# Drone.net
KiCad netlist of a schematic drawn in EAGLE
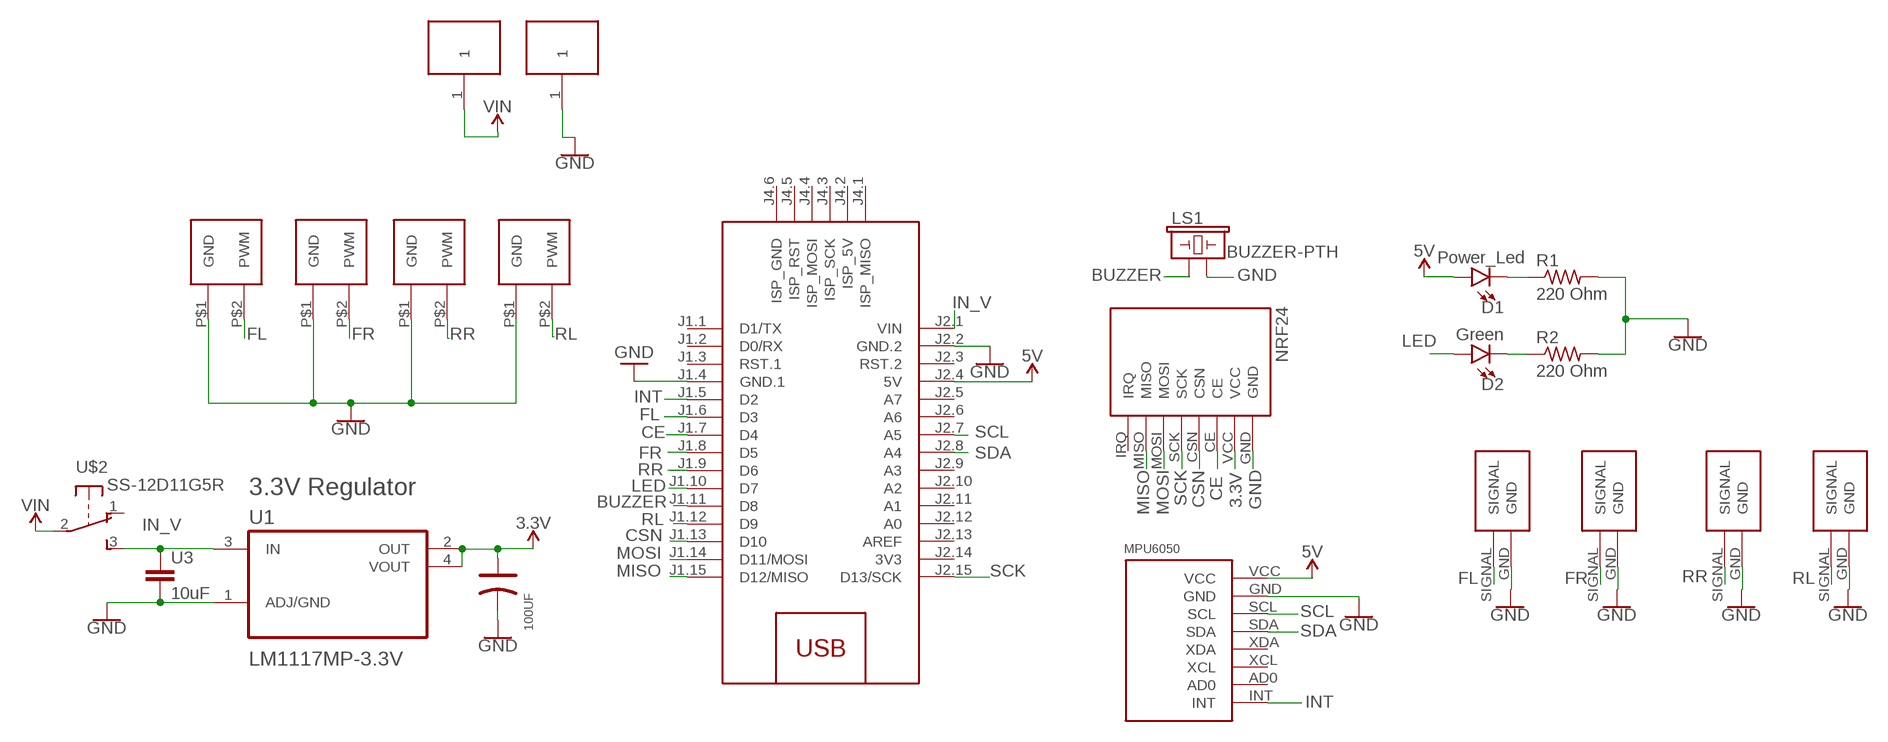
[diagram p0: schematic, sheet 1]

(export (version "E")
  (design (tool "Eeschema 10.0.6"))
  (components
    (comp (ref "D1")
      (value "Power_Led")
      (footprint "eagle-import:LED_5MM")
      (libsource (lib "eagle-import") (part "LED5MM"))
    )
    (comp (ref "D2")
      (value "Green")
      (footprint "eagle-import:LED_5MM")
      (libsource (lib "eagle-import") (part "LED5MM"))
    )
    (comp (ref "LS1")
      (value "BUZZER-PTH")
      (footprint "eagle-import:BUZZER-12MM")
      (libsource (lib "eagle-import") (part "BUZZER-PTH"))
    )
    (comp (ref "M1")
      (value "ARDUINO-NANO-3.0#ISP")
      (footprint "eagle-import:ARDUINO-NANO-3.0#ISP")
      (libsource (lib "eagle-import") (part "ARDUINO-NANO-3.0#ISP"))
    )
    (comp (ref "R1")
      (value "220 Ohm")
      (footprint "eagle-import:RES_1206")
      (fields
        (field (name "DIGIKEY_PART_NUMBER") "P0.0ETR-ND")
        (field (name "MANUFACTURER") "Panasonic Electronic Components")
        (field (name "MPN") "ERJ-8GEY0R00V")
        (field (name "CREATED_BY") "PCBLayout.com")
      )
      (libsource (lib "eagle-import") (part "ERJ-8GEY0R00V"))
    )
    (comp (ref "R2")
      (value "220 Ohm")
      (footprint "eagle-import:RES_1206")
      (fields
        (field (name "DIGIKEY_PART_NUMBER") "P0.0ETR-ND")
        (field (name "MANUFACTURER") "Panasonic Electronic Components")
        (field (name "MPN") "ERJ-8GEY0R00V")
        (field (name "CREATED_BY") "PCBLayout.com")
      )
      (libsource (lib "eagle-import") (part "ERJ-8GEY0R00V"))
    )
    (comp (ref "U$1")
      (value "MPU6050")
      (footprint "eagle-import:MPU6050")
      (libsource (lib "eagle-import") (part "MPU6050"))
    )
    (comp (ref "U$2")
      (value "SS-12D11G5R")
      (footprint "eagle-import:SWITCH")
      (libsource (lib "eagle-import") (part "SS-12D11G5R"))
    )
    (comp (ref "U$3")
      (value "PWM")
      (footprint "eagle-import:PWM")
      (libsource (lib "eagle-import") (part "PWM"))
    )
    (comp (ref "U$4")
      (value "PWM")
      (footprint "eagle-import:PWM")
      (libsource (lib "eagle-import") (part "PWM"))
    )
    (comp (ref "U$5")
      (value "NRF24")
      (footprint "eagle-import:NRF24")
      (libsource (lib "eagle-import") (part "NRF24"))
    )
    (comp (ref "U$6")
      (value "PWM")
      (footprint "eagle-import:PWM")
      (libsource (lib "eagle-import") (part "PWM"))
    )
    (comp (ref "U$7")
      (value "PWM")
      (footprint "eagle-import:PWM")
      (libsource (lib "eagle-import") (part "PWM"))
    )
    (comp (ref "U$8")
      (value "PAD")
      (footprint "eagle-import:PAD")
      (libsource (lib "eagle-import") (part "PAD"))
    )
    (comp (ref "U$9")
      (value "PAD")
      (footprint "eagle-import:PAD")
      (libsource (lib "eagle-import") (part "PAD"))
    )
    (comp (ref "U$10")
      (value "SIGNAL")
      (footprint "eagle-import:SIGNAL")
      (libsource (lib "eagle-import") (part "SIGNAL"))
    )
    (comp (ref "U$11")
      (value "SIGNAL")
      (footprint "eagle-import:SIGNAL")
      (libsource (lib "eagle-import") (part "SIGNAL"))
    )
    (comp (ref "U$12")
      (value "SIGNAL")
      (footprint "eagle-import:SIGNAL")
      (libsource (lib "eagle-import") (part "SIGNAL"))
    )
    (comp (ref "U$13")
      (value "SIGNAL")
      (footprint "eagle-import:SIGNAL")
      (libsource (lib "eagle-import") (part "SIGNAL"))
    )
    (comp (ref "U1")
      (value "LM1117MP-3.3V")
      (footprint "eagle-import:SOT230P700X180-4N")
      (libsource (lib "eagle-import") (part "LM1117MP-5.0"))
    )
    (comp (ref "U2")
      (value "100UF")
      (footprint "eagle-import:8X10MM")
      (libsource (lib "eagle-import") (part "100UF"))
    )
    (comp (ref "U3")
      (value "10uF")
      (footprint "eagle-import:1206")
      (libsource (lib "eagle-import") (part "10UF-1206-6.3V-20%"))
    )
  )
  (nets
    (net (code "1") (name "/3V3") (class "Default")
      (node (ref "M1") (pin "J2.14") (pinfunction "3V3_J2.14") (pintype "power_in"))
    )
    (net (code "2") (name "/BUZZER") (class "Default")
      (node (ref "LS1") (pin "+") (pinfunction "1_+") (pintype "passive"))
      (node (ref "M1") (pin "J1.11") (pinfunction "D8_J1.11") (pintype "bidirectional"))
    )
    (net (code "3") (name "/CE") (class "Default")
      (node (ref "M1") (pin "J1.7") (pinfunction "D4_J1.7") (pintype "bidirectional"))
      (node (ref "U$5") (pin "CE") (pinfunction "CE_CE") (pintype "bidirectional"))
    )
    (net (code "4") (name "/CSN") (class "Default")
      (node (ref "M1") (pin "J1.13") (pinfunction "D10_J1.13") (pintype "bidirectional"))
      (node (ref "U$5") (pin "CSN") (pinfunction "CSN_CSN") (pintype "bidirectional"))
    )
    (net (code "5") (name "/FL") (class "Default")
      (node (ref "M1") (pin "J1.6") (pinfunction "D3_J1.6") (pintype "bidirectional"))
      (node (ref "U$10") (pin "SIGNAL") (pinfunction "SIGNAL_SIGNAL") (pintype "bidirectional"))
      (node (ref "U$3") (pin "P$2") (pinfunction "PWM_P$2") (pintype "bidirectional"))
    )
    (net (code "6") (name "/FR") (class "Default")
      (node (ref "M1") (pin "J1.8") (pinfunction "D5_J1.8") (pintype "bidirectional"))
      (node (ref "U$11") (pin "SIGNAL") (pinfunction "SIGNAL_SIGNAL") (pintype "bidirectional"))
      (node (ref "U$4") (pin "P$2") (pinfunction "PWM_P$2") (pintype "bidirectional"))
    )
    (net (code "7") (name "/INT") (class "Default")
      (node (ref "M1") (pin "J1.5") (pinfunction "D2_J1.5") (pintype "bidirectional"))
      (node (ref "U$1") (pin "INT") (pinfunction "INT_INT") (pintype "bidirectional"))
    )
    (net (code "8") (name "/IN_V") (class "Default")
      (node (ref "M1") (pin "J2.1") (pinfunction "VIN_J2.1") (pintype "power_in"))
      (node (ref "U$2") (pin "3") (pinfunction "S_3") (pintype "passive"))
      (node (ref "U1") (pin "3") (pinfunction "IN_3") (pintype "input"))
      (node (ref "U3") (pin "1") (pinfunction "1_1") (pintype "passive"))
    )
    (net (code "9") (name "/LED") (class "Default")
      (node (ref "D2") (pin "A") (pinfunction "A_A") (pintype "passive"))
      (node (ref "M1") (pin "J1.10") (pinfunction "D7_J1.10") (pintype "bidirectional"))
    )
    (net (code "10") (name "/MISO") (class "Default")
      (node (ref "M1") (pin "J1.15") (pinfunction "D12/MISO_J1.15") (pintype "bidirectional"))
      (node (ref "U$5") (pin "MISO") (pinfunction "MISO_MISO") (pintype "bidirectional"))
    )
    (net (code "11") (name "/MOSI") (class "Default")
      (node (ref "M1") (pin "J1.14") (pinfunction "D11/MOSI_J1.14") (pintype "bidirectional"))
      (node (ref "U$5") (pin "MOSI") (pinfunction "MOSI_MOSI") (pintype "bidirectional"))
    )
    (net (code "12") (name "/RL") (class "Default")
      (node (ref "M1") (pin "J1.12") (pinfunction "D9_J1.12") (pintype "bidirectional"))
      (node (ref "U$13") (pin "SIGNAL") (pinfunction "SIGNAL_SIGNAL") (pintype "bidirectional"))
      (node (ref "U$7") (pin "P$2") (pinfunction "PWM_P$2") (pintype "bidirectional"))
    )
    (net (code "13") (name "/RR") (class "Default")
      (node (ref "M1") (pin "J1.9") (pinfunction "D6_J1.9") (pintype "bidirectional"))
      (node (ref "U$12") (pin "SIGNAL") (pinfunction "SIGNAL_SIGNAL") (pintype "bidirectional"))
      (node (ref "U$6") (pin "P$2") (pinfunction "PWM_P$2") (pintype "bidirectional"))
    )
    (net (code "14") (name "/SCK") (class "Default")
      (node (ref "M1") (pin "J2.15") (pinfunction "D13/SCK_J2.15") (pintype "bidirectional"))
      (node (ref "U$5") (pin "SCK") (pinfunction "SCK_SCK") (pintype "bidirectional"))
    )
    (net (code "15") (name "/SCL") (class "Default")
      (node (ref "M1") (pin "J2.7") (pinfunction "A5_J2.7") (pintype "bidirectional"))
      (node (ref "U$1") (pin "SCL") (pinfunction "SCL_SCL") (pintype "bidirectional"))
    )
    (net (code "16") (name "/SDA") (class "Default")
      (node (ref "M1") (pin "J2.8") (pinfunction "A4_J2.8") (pintype "bidirectional"))
      (node (ref "U$1") (pin "SDA") (pinfunction "SDA_SDA") (pintype "bidirectional"))
    )
    (net (code "17") (name "3.3V") (class "Default")
      (node (ref "U$5") (pin "VCC") (pinfunction "VCC_VCC") (pintype "bidirectional"))
      (node (ref "U1") (pin "2") (pinfunction "OUT_2") (pintype "output"))
      (node (ref "U1") (pin "4") (pinfunction "VOUT_4") (pintype "output"))
      (node (ref "U2") (pin "1") (pinfunction "+_1") (pintype "passive"))
    )
    (net (code "18") (name "5V") (class "Default")
      (node (ref "D1") (pin "A") (pinfunction "A_A") (pintype "passive"))
      (node (ref "M1") (pin "J2.4") (pinfunction "5V_J2.4") (pintype "power_in"))
      (node (ref "U$1") (pin "VCC") (pinfunction "VCC_VCC") (pintype "bidirectional"))
    )
    (net (code "19") (name "GND") (class "Default")
      (node (ref "LS1") (pin "-") (pinfunction "2_-") (pintype "passive"))
      (node (ref "M1") (pin "J1.4") (pinfunction "GND.1_J1.4") (pintype "power_in"))
      (node (ref "M1") (pin "J2.2") (pinfunction "GND.2_J2.2") (pintype "power_in"))
      (node (ref "R1") (pin "2") (pinfunction "2_2") (pintype "passive"))
      (node (ref "R2") (pin "2") (pinfunction "2_2") (pintype "passive"))
      (node (ref "U$1") (pin "GND") (pinfunction "GND_GND") (pintype "bidirectional"))
      (node (ref "U$10") (pin "GND") (pinfunction "GND_GND") (pintype "bidirectional"))
      (node (ref "U$11") (pin "GND") (pinfunction "GND_GND") (pintype "bidirectional"))
      (node (ref "U$12") (pin "GND") (pinfunction "GND_GND") (pintype "bidirectional"))
      (node (ref "U$13") (pin "GND") (pinfunction "GND_GND") (pintype "bidirectional"))
      (node (ref "U$3") (pin "P$1") (pinfunction "GND_P$1") (pintype "bidirectional"))
      (node (ref "U$4") (pin "P$1") (pinfunction "GND_P$1") (pintype "bidirectional"))
      (node (ref "U$5") (pin "GND") (pinfunction "GND_GND") (pintype "bidirectional"))
      (node (ref "U$6") (pin "P$1") (pinfunction "GND_P$1") (pintype "bidirectional"))
      (node (ref "U$7") (pin "P$1") (pinfunction "GND_P$1") (pintype "bidirectional"))
      (node (ref "U$9") (pin "1") (pinfunction "1_1") (pintype "bidirectional"))
      (node (ref "U1") (pin "1") (pinfunction "ADJ/GND_1") (pintype "bidirectional"))
      (node (ref "U2") (pin "2") (pinfunction "-_2") (pintype "passive"))
      (node (ref "U3") (pin "2") (pinfunction "2_2") (pintype "passive"))
    )
    (net (code "20") (name "Net-(D1-C)") (class "Default")
      (node (ref "D1") (pin "K") (pinfunction "C_K") (pintype "passive"))
      (node (ref "R1") (pin "1") (pinfunction "1_1") (pintype "passive"))
    )
    (net (code "21") (name "Net-(D2-C)") (class "Default")
      (node (ref "D2") (pin "K") (pinfunction "C_K") (pintype "passive"))
      (node (ref "R2") (pin "1") (pinfunction "1_1") (pintype "passive"))
    )
    (net (code "22") (name "VIN") (class "Default")
      (node (ref "U$2") (pin "2") (pinfunction "P_2") (pintype "passive"))
      (node (ref "U$8") (pin "1") (pinfunction "1_1") (pintype "bidirectional"))
    )
    (net (code "23") (name "unconnected-(M1-A0-PadJ2.12)") (class "Default")
      (node (ref "M1") (pin "J2.12") (pinfunction "A0_J2.12") (pintype "bidirectional"))
    )
    (net (code "24") (name "unconnected-(M1-A1-PadJ2.11)") (class "Default")
      (node (ref "M1") (pin "J2.11") (pinfunction "A1_J2.11") (pintype "bidirectional"))
    )
    (net (code "25") (name "unconnected-(M1-A2-PadJ2.10)") (class "Default")
      (node (ref "M1") (pin "J2.10") (pinfunction "A2_J2.10") (pintype "bidirectional"))
    )
    (net (code "26") (name "unconnected-(M1-A3-PadJ2.9)") (class "Default")
      (node (ref "M1") (pin "J2.9") (pinfunction "A3_J2.9") (pintype "bidirectional"))
    )
    (net (code "27") (name "unconnected-(M1-A6-PadJ2.6)") (class "Default")
      (node (ref "M1") (pin "J2.6") (pinfunction "A6_J2.6") (pintype "bidirectional"))
    )
    (net (code "28") (name "unconnected-(M1-A7-PadJ2.5)") (class "Default")
      (node (ref "M1") (pin "J2.5") (pinfunction "A7_J2.5") (pintype "bidirectional"))
    )
    (net (code "29") (name "unconnected-(M1-AREF-PadJ2.13)") (class "Default")
      (node (ref "M1") (pin "J2.13") (pinfunction "AREF_J2.13") (pintype "bidirectional"))
    )
    (net (code "30") (name "unconnected-(M1-D0{slash}RX-PadJ1.2)") (class "Default")
      (node (ref "M1") (pin "J1.2") (pinfunction "D0/RX_J1.2") (pintype "bidirectional"))
    )
    (net (code "31") (name "unconnected-(M1-D1{slash}TX-PadJ1.1)") (class "Default")
      (node (ref "M1") (pin "J1.1") (pinfunction "D1/TX_J1.1") (pintype "bidirectional"))
    )
    (net (code "32") (name "unconnected-(M1-ISP_5V-PadJ4.2)") (class "Default")
      (node (ref "M1") (pin "J4.2") (pinfunction "ISP_5V_J4.2") (pintype "bidirectional"))
    )
    (net (code "33") (name "unconnected-(M1-ISP_GND-PadJ4.6)") (class "Default")
      (node (ref "M1") (pin "J4.6") (pinfunction "ISP_GND_J4.6") (pintype "bidirectional"))
    )
    (net (code "34") (name "unconnected-(M1-ISP_MISO-PadJ4.1)") (class "Default")
      (node (ref "M1") (pin "J4.1") (pinfunction "ISP_MISO_J4.1") (pintype "bidirectional"))
    )
    (net (code "35") (name "unconnected-(M1-ISP_MOSI-PadJ4.4)") (class "Default")
      (node (ref "M1") (pin "J4.4") (pinfunction "ISP_MOSI_J4.4") (pintype "bidirectional"))
    )
    (net (code "36") (name "unconnected-(M1-ISP_RST-PadJ4.5)") (class "Default")
      (node (ref "M1") (pin "J4.5") (pinfunction "ISP_RST_J4.5") (pintype "bidirectional"))
    )
    (net (code "37") (name "unconnected-(M1-ISP_SCK-PadJ4.3)") (class "Default")
      (node (ref "M1") (pin "J4.3") (pinfunction "ISP_SCK_J4.3") (pintype "bidirectional"))
    )
    (net (code "38") (name "unconnected-(M1-RST.1-PadJ1.3)") (class "Default")
      (node (ref "M1") (pin "J1.3") (pinfunction "RST.1_J1.3") (pintype "bidirectional"))
    )
    (net (code "39") (name "unconnected-(M1-RST.2-PadJ2.3)") (class "Default")
      (node (ref "M1") (pin "J2.3") (pinfunction "RST.2_J2.3") (pintype "bidirectional"))
    )
    (net (code "40") (name "unconnected-(U$1-PadAD0)") (class "Default")
      (node (ref "U$1") (pin "AD0") (pinfunction "AD0_AD0") (pintype "bidirectional"))
    )
    (net (code "41") (name "unconnected-(U$1-PadXCL)") (class "Default")
      (node (ref "U$1") (pin "XCL") (pinfunction "XCL_XCL") (pintype "bidirectional"))
    )
    (net (code "42") (name "unconnected-(U$1-PadXDA)") (class "Default")
      (node (ref "U$1") (pin "XDA") (pinfunction "XDA_XDA") (pintype "bidirectional"))
    )
    (net (code "43") (name "unconnected-(U$2-O-Pad1)") (class "Default")
      (node (ref "U$2") (pin "1") (pinfunction "O_1") (pintype "passive"))
    )
    (net (code "44") (name "unconnected-(U$5-PadIRQ)") (class "Default")
      (node (ref "U$5") (pin "IRQ") (pinfunction "IRQ_IRQ") (pintype "bidirectional"))
    )
  )
)
